# 05_-SW420.net
KiCad netlist of a schematic drawn in Altium Designer
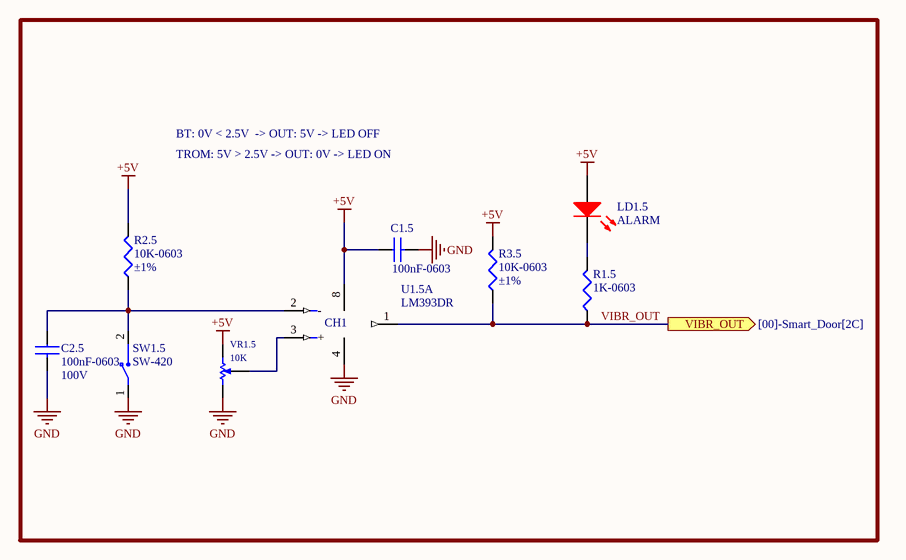
[diagram p0: [05]-SW420.SchDoc]

(export (version "E")
  (design (tool "Eeschema 10.0.6"))
  (components
    (comp (ref "C1.5")
      (value "100nF-0603")
      (footprint "CAP0603")
      (description "CAP CER 0.1UF 100V X7R 0603")
      (fields
        (field (name "MANUFACTURER") "Yageo")
        (field (name "MANUFACTURER PART NUMBER") "CC0603KRX7R0BB104")
      )
      (libsource (lib "Indruino") (part "CC0603KRX7R0BB104"))
    )
    (comp (ref "C2.5")
      (value "100nF-0603")
      (footprint "CAP0603")
      (description "CAP CER 0.1UF 100V X7R 0603")
      (fields
        (field (name "MANUFACTURER") "Yageo")
        (field (name "MANUFACTURER PART NUMBER") "CC0603KRX7R0BB104")
        (field (name "VOLTAGE - RATED") "100V")
      )
      (libsource (lib "Indruino") (part "CC0603KRX7R0BB104"))
    )
    (comp (ref "LD1.5")
      (value "ALARM")
      (footprint "Indruino:LED_SMD0603_RED")
      (description "LED RED CLEAR 0603 SMD")
      (fields
        (field (name "MANUFACTURER") "Lite-On Inc.")
        (field (name "MANUFACTURER PART NUMBER") "LTST-C191KRKT")
      )
      (libsource (lib "Indruino") (part "LED_LTST-C191KRKT"))
    )
    (comp (ref "R1.5")
      (value "1K-0603")
      (footprint "RES0603")
      (description "RES SMD 1K OHM 5% 1/10W 0603")
      (fields (field (name "TOLERANCE") "±5%"))
      (libsource (lib "Indruino") (part "RC0603JR-071KL"))
    )
    (comp (ref "R2.5")
      (value "10K-0603")
      (footprint "RES0603")
      (description "RES SMD 10K OHM 1% 1/10W 0603")
      (fields
        (field (name "MANUFACTURER") "Yageo")
        (field (name "MANUFACTURER PART NUMBER") "RC0603FR-0710KL")
        (field (name "TOLERANCE") "±1%")
      )
      (libsource (lib "Indruino") (part "RC0603FR-0710KL"))
    )
    (comp (ref "R3.5")
      (value "10K-0603")
      (footprint "RES0603")
      (description "RES SMD 10K OHM 1% 1/10W 0603")
      (fields
        (field (name "MANUFACTURER") "Yageo")
        (field (name "MANUFACTURER PART NUMBER") "RC0603FR-0710KL")
        (field (name "TOLERANCE") "±1%")
      )
      (libsource (lib "Indruino") (part "RC0603FR-0710KL"))
    )
    (comp (ref "SW1.5")
      (value "SW-420")
      (footprint "AZ_Lib:SW-420")
      (libsource (lib "AZ_Lib") (part "SW-420"))
    )
    (comp (ref "U1.5")
      (value "LM393DR")
      (footprint "AZ_Lib:SOP8")
      (description "Analogue Comparator, Dual, Differential, 2, 1.3 s, 2V to 36V, SOIC, 8")
      (libsource (lib "AZ_Lib") (part "LM393DR"))
    )
    (comp (ref "VR1.5")
      (value "10K")
      (footprint "MinhTien_PCBLib:VARIABLE RESISTOR_3362P")
      (description "Square Trimming Potentiometer")
      (libsource (lib "MinhTien_SCHLib") (part "Variable Resistor"))
    )
  )
  (nets
    (net (code "1") (name "+5V") (class "Default")
      (node (ref "C1.5") (pin "1") (pinfunction "1_1") (pintype "passive"))
      (node (ref "LD1.5") (pin "1") (pinfunction "A_1") (pintype "passive"))
      (node (ref "R2.5") (pin "2") (pinfunction "2_2") (pintype "passive"))
      (node (ref "R3.5") (pin "2") (pinfunction "2_2") (pintype "passive"))
      (node (ref "U1.5") (pin "8") (pinfunction "VCC_8") (pintype "power_in"))
      (node (ref "VR1.5") (pin "1") (pinfunction "1_1") (pintype "passive"))
    )
    (net (code "2") (name "/VIBR_OUT") (class "Default")
      (node (ref "R1.5") (pin "1") (pinfunction "1_1") (pintype "passive"))
      (node (ref "R3.5") (pin "1") (pinfunction "1_1") (pintype "passive"))
      (node (ref "U1.5") (pin "1") (pinfunction "OUT1_1") (pintype "output"))
    )
    (net (code "3") (name "GND") (class "Default")
      (node (ref "C1.5") (pin "2") (pinfunction "2_2") (pintype "passive"))
      (node (ref "C2.5") (pin "2") (pinfunction "2_2") (pintype "passive"))
      (node (ref "SW1.5") (pin "1") (pinfunction "1_1") (pintype "passive"))
      (node (ref "U1.5") (pin "4") (pinfunction "GND_4") (pintype "power_in"))
      (node (ref "VR1.5") (pin "3") (pinfunction "3_3") (pintype "passive"))
    )
    (net (code "4") (name "Net-(LD1.5-K)") (class "Default")
      (node (ref "LD1.5") (pin "2") (pinfunction "K_2") (pintype "passive"))
      (node (ref "R1.5") (pin "2") (pinfunction "2_2") (pintype "passive"))
    )
    (net (code "5") (name "Net-(U1.5A-+)") (class "Default")
      (node (ref "U1.5") (pin "3") (pinfunction "+_3") (pintype "input"))
      (node (ref "VR1.5") (pin "2") (pinfunction "2_2") (pintype "passive"))
    )
    (net (code "6") (name "Net-(U1.5A--)") (class "Default")
      (node (ref "C2.5") (pin "1") (pinfunction "1_1") (pintype "passive"))
      (node (ref "R2.5") (pin "1") (pinfunction "1_1") (pintype "passive"))
      (node (ref "SW1.5") (pin "2") (pinfunction "2_2") (pintype "passive"))
      (node (ref "U1.5") (pin "2") (pinfunction "-_2") (pintype "input"))
    )
  )
)
